# headers.net
KiCad netlist of a schematic drawn in Altium Designer
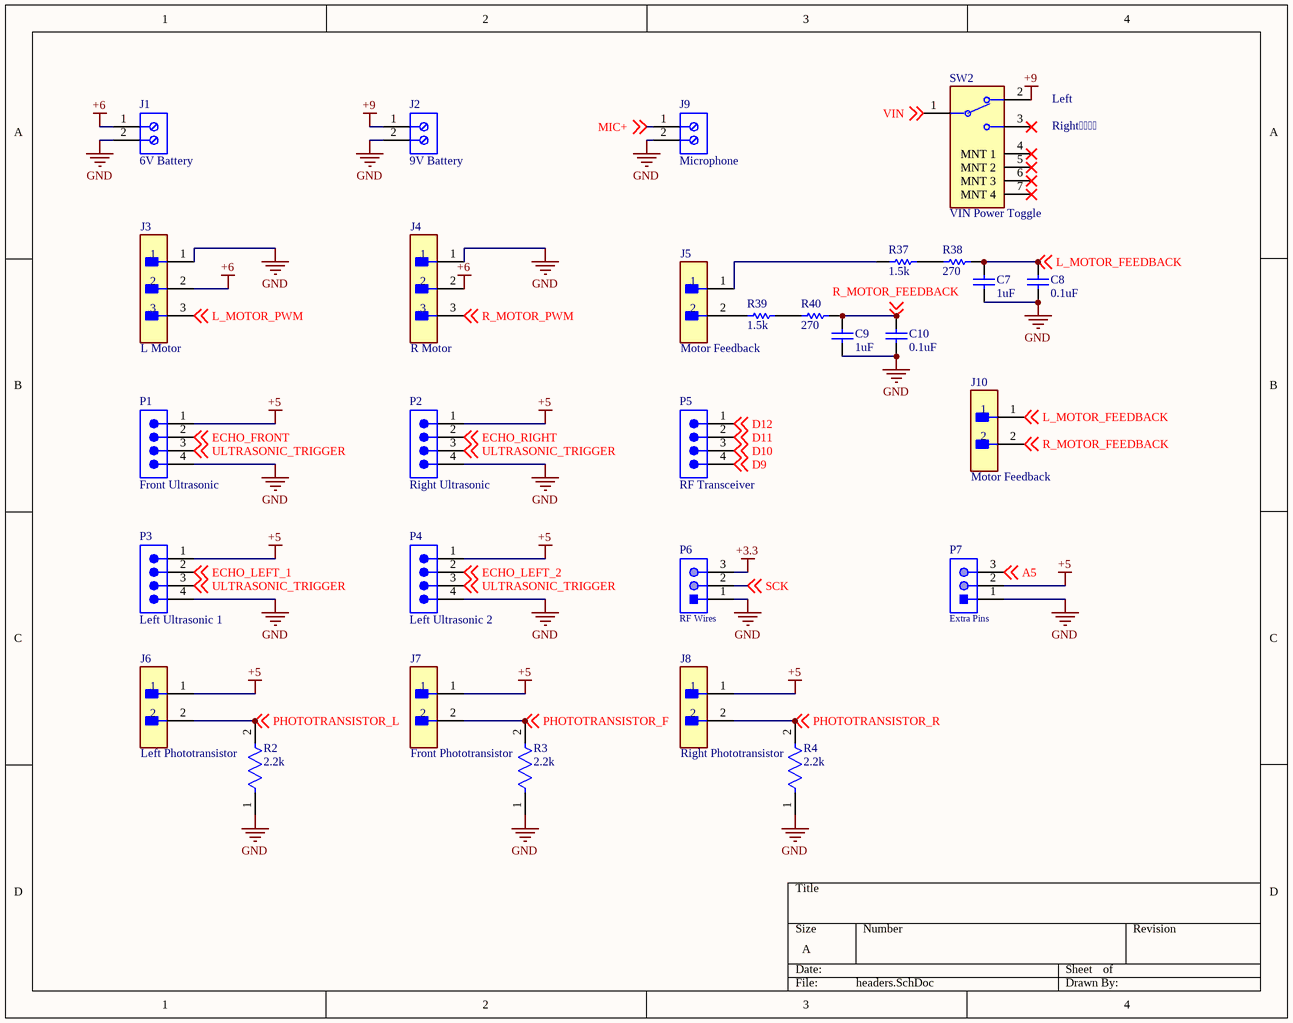
[diagram p0: headers.SchDoc]

(export (version "E")
  (design (tool "Eeschema 10.0.6"))
  (components
    (comp (ref "C7")
      (value "1uF")
      (footprint "CAPC2013X145X50LL20T25")
      (fields (field (name "MANUFACTURER") "Kemet") (field (name "PART NUMBER") "C0805C105K4PACTU"))
      (libsource (lib "Altium Content Vault") (part "CAP"))
    )
    (comp (ref "C8")
      (value "0.1uF")
      (footprint "CAPC2013X145X50LL20T25")
      (fields (field (name "MANUFACTURER") "Kemet") (field (name "PART NUMBER") "C0805C105K4PACTU"))
      (libsource (lib "Altium Content Vault") (part "CAP"))
    )
    (comp (ref "C9")
      (value "1uF")
      (footprint "CAPC2013X145X50LL20T25")
      (fields (field (name "MANUFACTURER") "Kemet") (field (name "PART NUMBER") "C0805C105K4PACTU"))
      (libsource (lib "Altium Content Vault") (part "CAP"))
    )
    (comp (ref "C10")
      (value "0.1uF")
      (footprint "CAPC2013X145X50LL20T25")
      (fields (field (name "MANUFACTURER") "Kemet") (field (name "PART NUMBER") "C0805C105K4PACTU"))
      (libsource (lib "Altium Content Vault") (part "CAP"))
    )
    (comp (ref "J1")
      (value "6V Battery")
      (footprint "691103110002")
      (description "Series 1031 - 3.50 mm Horizontal Entry Modular with Pressure Clamp WR-TBL, 2 pin")
      (fields
        (field (name "MANUFACTURER") "Wurth Elektronik")
        (field (name "PART NUMBER") "691103110002")
        (field (name "PUBLISHER") "WurthElektronik")
      )
      (libsource (lib "Altium Content Vault") (part "WE-CN-1P-F-TB2"))
    )
    (comp (ref "J2")
      (value "9V Battery")
      (footprint "691103110002")
      (description "Series 1031 - 3.50 mm Horizontal Entry Modular with Pressure Clamp WR-TBL, 2 pin")
      (fields
        (field (name "MANUFACTURER") "Wurth Elektronik")
        (field (name "PART NUMBER") "691103110002")
        (field (name "PUBLISHER") "WurthElektronik")
      )
      (libsource (lib "Altium Content Vault") (part "WE-CN-1P-F-TB2"))
    )
    (comp (ref "J3")
      (value "L Motor")
      (footprint "FP-5-104935-3-MFG")
      (description "CONN HEADER R/A 3POS 2.54MM")
      (fields (field (name "MPN") "5-104935-3"))
      (libsource (lib "Altium Content Vault") (part "0d3f023dd272f625e17a2be33dea85f"))
    )
    (comp (ref "J4")
      (value "R Motor")
      (footprint "FP-5-104935-3-MFG")
      (description "CONN HEADER R/A 3POS 2.54MM")
      (fields (field (name "MPN") "5-104935-3"))
      (libsource (lib "Altium Content Vault") (part "0d3f023dd272f625e17a2be33dea85f"))
    )
    (comp (ref "J5")
      (value "Motor Feedback")
      (footprint "FP-M20-9990246-MFG")
      (description "CONN HEADER VERT 2POS 2.54MM")
      (fields
        (field (name "OCTOPART") "https://octopart.com/m20-9990246-harwin-2590635")
        (field (name "MANUFACTURER") "Harwin")
      )
      (libsource (lib "Altium Content Vault") (part "3bc925449376181038e59eaffc5286c"))
    )
    (comp (ref "J6")
      (value "Left Phototransistor")
      (footprint "FP-M20-9990246-MFG")
      (description "Connector Header Through Hole 2 position 0.100\" (2.54mm)")
      (fields (field (name "OCTOPART") "https://octopart.com/m20-9990246-harwin-2590635"))
      (libsource (lib "Altium Content Vault") (part "3bc925449376181038e59eaffc5286c"))
    )
    (comp (ref "J7")
      (value "Front Phototransistor")
      (footprint "FP-M20-9990246-MFG")
      (description "Connector Header Through Hole 2 position 0.100\" (2.54mm)")
      (fields (field (name "OCTOPART") "https://octopart.com/m20-9990246-harwin-2590635"))
      (libsource (lib "Altium Content Vault") (part "3bc925449376181038e59eaffc5286c"))
    )
    (comp (ref "J8")
      (value "Right Phototransistor")
      (footprint "FP-M20-9990246-MFG")
      (description "Connector Header Through Hole 2 position 0.100\" (2.54mm)")
      (fields (field (name "OCTOPART") "https://octopart.com/m20-9990246-harwin-2590635"))
      (libsource (lib "Altium Content Vault") (part "3bc925449376181038e59eaffc5286c"))
    )
    (comp (ref "J9")
      (value "Microphone")
      (footprint "691103110002")
      (description "Series 1031 - 3.50 mm Horizontal Entry Modular with Pressure Clamp WR-TBL, 2 pin")
      (fields
        (field (name "MANUFACTURER") "Wurth Elektronik")
        (field (name "PART NUMBER") "691103110002")
        (field (name "PUBLISHER") "WurthElektronik")
      )
      (libsource (lib "Altium Content Vault") (part "WE-CN-1P-F-TB2"))
    )
    (comp (ref "J10")
      (value "Motor Feedback")
      (footprint "FP-M20-9990246-MFG")
      (description "CONN HEADER VERT 2POS 2.54MM")
      (fields
        (field (name "OCTOPART") "https://octopart.com/m20-9990246-harwin-2590635")
        (field (name "MANUFACTURER") "Harwin")
      )
      (libsource (lib "Altium Content Vault") (part "3bc925449376181038e59eaffc5286c"))
    )
    (comp (ref "P1")
      (value "Front Ultrasonic")
      (footprint "SMTC-TSW-104-08-X-S")
      (description "0.025\" SQ Post Header, Through-hole, Vertical, -55 to 125 degC, 2.54 mm Pitch, 4-Pin, Male, RoHS")
      (fields (field (name "MANUFACTURER") "Samtec") (field (name "PARTNUMBER") "TSW-104-08-F-S"))
      (libsource (lib "Altium Content Vault") (part "SMTC-TSW-104-08-X-S"))
    )
    (comp (ref "P2")
      (value "Right Ultrasonic")
      (footprint "SMTC-TSW-104-08-X-S")
      (description "0.025\" SQ Post Header, Through-hole, Vertical, -55 to 125 degC, 2.54 mm Pitch, 4-Pin, Male, RoHS")
      (fields (field (name "MANUFACTURER") "Samtec") (field (name "PARTNUMBER") "TSW-104-08-F-S"))
      (libsource (lib "Altium Content Vault") (part "SMTC-TSW-104-08-X-S"))
    )
    (comp (ref "P3")
      (value "Left Ultrasonic 1")
      (footprint "SMTC-TSW-104-08-X-S")
      (description "0.025\" SQ Post Header, Through-hole, Vertical, -55 to 125 degC, 2.54 mm Pitch, 4-Pin, Male, RoHS")
      (fields (field (name "MANUFACTURER") "Samtec") (field (name "PARTNUMBER") "TSW-104-08-F-S"))
      (libsource (lib "Altium Content Vault") (part "SMTC-TSW-104-08-X-S"))
    )
    (comp (ref "P4")
      (value "Left Ultrasonic 2")
      (footprint "SMTC-TSW-104-08-X-S")
      (description "0.025\" SQ Post Header, Through-hole, Vertical, -55 to 125 degC, 2.54 mm Pitch, 4-Pin, Male, RoHS")
      (fields (field (name "MANUFACTURER") "Samtec") (field (name "PARTNUMBER") "TSW-104-08-F-S"))
      (libsource (lib "Altium Content Vault") (part "SMTC-TSW-104-08-X-S"))
    )
    (comp (ref "P5")
      (value "RF Transceiver")
      (footprint "SMTC-TSW-104-08-X-S")
      (description "0.025\" SQ Post Header, Through-hole, Vertical, -55 to 125 degC, 2.54 mm Pitch, 4-Pin, Male, RoHS")
      (fields (field (name "MANUFACTURER") "Samtec") (field (name "PARTNUMBER") "TSW-104-08-F-S"))
      (libsource (lib "Altium Content Vault") (part "SMTC-TSW-104-08-X-S"))
    )
    (comp (ref "P6")
      (value "RF Wires")
      (footprint "61300311121")
      (description "THT Vertical Pin Header WR-PHD, Pitch 2.54 mm, Single Row, 3 pins")
      (fields
        (field (name "PART NUMBER") "61300311121")
        (field (name "MANUFACTURER") "Wurth Elektronik")
        (field (name "PUBLISHER") "WurthElektronik")
      )
      (libsource (lib "Altium Content Vault") (part "WE-CN-1P-M-R3"))
    )
    (comp (ref "P7")
      (value "Extra Pins")
      (footprint "61300311121")
      (description "THT Vertical Pin Header WR-PHD, Pitch 2.54 mm, Single Row, 3 pins")
      (fields
        (field (name "PART NUMBER") "61300311121")
        (field (name "MANUFACTURER") "Wurth Elektronik")
        (field (name "PUBLISHER") "WurthElektronik")
      )
      (libsource (lib "Altium Content Vault") (part "WE-CN-1P-M-R3"))
    )
    (comp (ref "R2")
      (value "2.2k")
      (footprint "FP-CRCW0805-e3-IPC_B")
      (description "RES Thick Film, 2.2kΩ, 1%, 0.125W, 100ppm/°C, 0805")
      (fields (field (name "TOLERANCE") "1%") (field (name "MPN") "CRCW08052K20FKEA"))
      (libsource (lib "Altium Content Vault") (part "1029c3af85768c4190bb7ad29bc67b5"))
    )
    (comp (ref "R3")
      (value "2.2k")
      (footprint "FP-CRCW0805-e3-IPC_B")
      (description "RES Thick Film, 2.2kΩ, 1%, 0.125W, 100ppm/°C, 0805")
      (fields (field (name "TOLERANCE") "1%") (field (name "MPN") "CRCW08052K20FKEA"))
      (libsource (lib "Altium Content Vault") (part "1029c3af85768c4190bb7ad29bc67b5"))
    )
    (comp (ref "R4")
      (value "2.2k")
      (footprint "FP-CRCW0805-e3-IPC_B")
      (description "RES Thick Film, 2.2kΩ, 1%, 0.125W, 100ppm/°C, 0805")
      (fields (field (name "TOLERANCE") "1%") (field (name "MPN") "CRCW08052K20FKEA"))
      (libsource (lib "Altium Content Vault") (part "1029c3af85768c4190bb7ad29bc67b5"))
    )
    (comp (ref "R37")
      (value "1.5k")
      (footprint "RESC1609X50X30NL8T20")
      (description "Chip Resistor, 10 KOhm, +/- 1%, 100 mW, -55 to 155 degC, 0603 (1608 Metric), RoHS, Tape and Reel")
      (fields (field (name "MANUFACTURER") "Vishay Semiconductor"))
      (libsource (lib "Altium Content Vault") (part "RES-2"))
    )
    (comp (ref "R38")
      (value "270")
      (footprint "RESC1609X50X30NL8T20")
      (description "Chip Resistor, 10 KOhm, +/- 1%, 100 mW, -55 to 155 degC, 0603 (1608 Metric), RoHS, Tape and Reel")
      (fields (field (name "MANUFACTURER") "Vishay Semiconductor"))
      (libsource (lib "Altium Content Vault") (part "RES-2"))
    )
    (comp (ref "R39")
      (value "1.5k")
      (footprint "RESC1609X50X30NL8T20")
      (description "Chip Resistor, 10 KOhm, +/- 1%, 100 mW, -55 to 155 degC, 0603 (1608 Metric), RoHS, Tape and Reel")
      (fields (field (name "MANUFACTURER") "Vishay Semiconductor"))
      (libsource (lib "Altium Content Vault") (part "RES-2"))
    )
    (comp (ref "R40")
      (value "270")
      (footprint "RESC1609X50X30NL8T20")
      (description "Chip Resistor, 10 KOhm, +/- 1%, 100 mW, -55 to 155 degC, 0603 (1608 Metric), RoHS, Tape and Reel")
      (fields (field (name "MANUFACTURER") "Vishay Semiconductor"))
      (libsource (lib "Altium Content Vault") (part "RES-2"))
    )
    (comp (ref "SW2")
      (value "VIN Power Toggle")
      (footprint "FP-PCM12SMTR-MFG")
      (description "SWITCH SLIDE SPDT 300MA 6V")
      (fields (field (name "MPN") "PCM12SMTR"))
      (libsource (lib "Altium Content Vault") (part "1a3f67d7e2b5469b171eeab59ffb4d2"))
    )
  )
  (nets
    (net (code "1") (name "+3.3") (class "Default")
      (node (ref "P6") (pin "3") (pinfunction "3_3") (pintype "passive"))
    )
    (net (code "2") (name "+5") (class "Default")
      (node (ref "J6") (pin "1") (pinfunction "1_1") (pintype "passive"))
      (node (ref "J7") (pin "1") (pinfunction "1_1") (pintype "passive"))
      (node (ref "J8") (pin "1") (pinfunction "1_1") (pintype "passive"))
      (node (ref "P1") (pin "1") (pinfunction "1_1") (pintype "passive"))
      (node (ref "P2") (pin "1") (pinfunction "1_1") (pintype "passive"))
      (node (ref "P3") (pin "1") (pinfunction "1_1") (pintype "passive"))
      (node (ref "P4") (pin "1") (pinfunction "1_1") (pintype "passive"))
      (node (ref "P7") (pin "2") (pinfunction "2_2") (pintype "passive"))
    )
    (net (code "3") (name "+6") (class "Default")
      (node (ref "J1") (pin "1") (pinfunction "1_1") (pintype "passive"))
      (node (ref "J3") (pin "2") (pinfunction "2_2") (pintype "passive"))
      (node (ref "J4") (pin "2") (pinfunction "2_2") (pintype "passive"))
    )
    (net (code "4") (name "+9") (class "Default")
      (node (ref "J2") (pin "1") (pinfunction "1_1") (pintype "passive"))
      (node (ref "SW2") (pin "2") (pinfunction "2_2") (pintype "passive"))
    )
    (net (code "5") (name "A5") (class "Default")
      (node (ref "P7") (pin "3") (pinfunction "3_3") (pintype "passive"))
    )
    (net (code "6") (name "D9") (class "Default")
      (node (ref "P5") (pin "4") (pinfunction "4_4") (pintype "passive"))
    )
    (net (code "7") (name "D10") (class "Default")
      (node (ref "P5") (pin "3") (pinfunction "3_3") (pintype "passive"))
    )
    (net (code "8") (name "D11") (class "Default")
      (node (ref "P5") (pin "2") (pinfunction "2_2") (pintype "passive"))
    )
    (net (code "9") (name "D12") (class "Default")
      (node (ref "P5") (pin "1") (pinfunction "1_1") (pintype "passive"))
    )
    (net (code "10") (name "ECHO_FRONT") (class "Default")
      (node (ref "P1") (pin "2") (pinfunction "2_2") (pintype "passive"))
    )
    (net (code "11") (name "ECHO_LEFT_1") (class "Default")
      (node (ref "P3") (pin "2") (pinfunction "2_2") (pintype "passive"))
    )
    (net (code "12") (name "ECHO_LEFT_2") (class "Default")
      (node (ref "P4") (pin "2") (pinfunction "2_2") (pintype "passive"))
    )
    (net (code "13") (name "ECHO_RIGHT") (class "Default")
      (node (ref "P2") (pin "2") (pinfunction "2_2") (pintype "passive"))
    )
    (net (code "14") (name "GND") (class "Default")
      (node (ref "C10") (pin "1") (pinfunction "1_1") (pintype "passive"))
      (node (ref "C7") (pin "1") (pinfunction "1_1") (pintype "passive"))
      (node (ref "C8") (pin "1") (pinfunction "1_1") (pintype "passive"))
      (node (ref "C9") (pin "2") (pinfunction "2_2") (pintype "passive"))
      (node (ref "J1") (pin "2") (pinfunction "2_2") (pintype "passive"))
      (node (ref "J2") (pin "2") (pinfunction "2_2") (pintype "passive"))
      (node (ref "J3") (pin "1") (pinfunction "1_1") (pintype "passive"))
      (node (ref "J4") (pin "1") (pinfunction "1_1") (pintype "passive"))
      (node (ref "J9") (pin "2") (pinfunction "2_2") (pintype "passive"))
      (node (ref "P1") (pin "4") (pinfunction "4_4") (pintype "passive"))
      (node (ref "P2") (pin "4") (pinfunction "4_4") (pintype "passive"))
      (node (ref "P3") (pin "4") (pinfunction "4_4") (pintype "passive"))
      (node (ref "P4") (pin "4") (pinfunction "4_4") (pintype "passive"))
      (node (ref "P6") (pin "1") (pinfunction "1_1") (pintype "passive"))
      (node (ref "P7") (pin "1") (pinfunction "1_1") (pintype "passive"))
      (node (ref "R2") (pin "1") (pinfunction "1_1") (pintype "passive"))
      (node (ref "R3") (pin "1") (pinfunction "1_1") (pintype "passive"))
      (node (ref "R4") (pin "1") (pinfunction "1_1") (pintype "passive"))
    )
    (net (code "15") (name "L_MOTOR_FEEDBACK") (class "Default")
      (node (ref "C7") (pin "2") (pinfunction "2_2") (pintype "passive"))
      (node (ref "C8") (pin "2") (pinfunction "2_2") (pintype "passive"))
      (node (ref "J10") (pin "1") (pinfunction "1_1") (pintype "passive"))
      (node (ref "R38") (pin "2") (pinfunction "2_2") (pintype "passive"))
    )
    (net (code "16") (name "L_MOTOR_PWM") (class "Default")
      (node (ref "J3") (pin "3") (pinfunction "3_3") (pintype "passive"))
    )
    (net (code "17") (name "MIC+") (class "Default")
      (node (ref "J9") (pin "1") (pinfunction "1_1") (pintype "passive"))
    )
    (net (code "18") (name "Net-(J5-Pad1)") (class "Default")
      (node (ref "J5") (pin "1") (pinfunction "1_1") (pintype "passive"))
      (node (ref "R37") (pin "1") (pinfunction "1_1") (pintype "passive"))
    )
    (net (code "19") (name "Net-(J5-Pad2)") (class "Default")
      (node (ref "J5") (pin "2") (pinfunction "2_2") (pintype "passive"))
      (node (ref "R39") (pin "1") (pinfunction "1_1") (pintype "passive"))
    )
    (net (code "20") (name "Net-(R37-Pad2)") (class "Default")
      (node (ref "R37") (pin "2") (pinfunction "2_2") (pintype "passive"))
      (node (ref "R38") (pin "1") (pinfunction "1_1") (pintype "passive"))
    )
    (net (code "21") (name "Net-(R39-Pad2)") (class "Default")
      (node (ref "R39") (pin "2") (pinfunction "2_2") (pintype "passive"))
      (node (ref "R40") (pin "1") (pinfunction "1_1") (pintype "passive"))
    )
    (net (code "22") (name "PHOTOTRANSISTOR_F") (class "Default")
      (node (ref "J7") (pin "2") (pinfunction "2_2") (pintype "passive"))
      (node (ref "R3") (pin "2") (pinfunction "2_2") (pintype "passive"))
    )
    (net (code "23") (name "PHOTOTRANSISTOR_L") (class "Default")
      (node (ref "J6") (pin "2") (pinfunction "2_2") (pintype "passive"))
      (node (ref "R2") (pin "2") (pinfunction "2_2") (pintype "passive"))
    )
    (net (code "24") (name "PHOTOTRANSISTOR_R") (class "Default")
      (node (ref "J8") (pin "2") (pinfunction "2_2") (pintype "passive"))
      (node (ref "R4") (pin "2") (pinfunction "2_2") (pintype "passive"))
    )
    (net (code "25") (name "R_MOTOR_FEEDBACK") (class "Default")
      (node (ref "C10") (pin "2") (pinfunction "2_2") (pintype "passive"))
      (node (ref "C9") (pin "1") (pinfunction "1_1") (pintype "passive"))
      (node (ref "J10") (pin "2") (pinfunction "2_2") (pintype "passive"))
      (node (ref "R40") (pin "2") (pinfunction "2_2") (pintype "passive"))
    )
    (net (code "26") (name "R_MOTOR_PWM") (class "Default")
      (node (ref "J4") (pin "3") (pinfunction "3_3") (pintype "passive"))
    )
    (net (code "27") (name "SCK") (class "Default")
      (node (ref "P6") (pin "2") (pinfunction "2_2") (pintype "passive"))
    )
    (net (code "28") (name "ULTRASONIC_TRIGGER") (class "Default")
      (node (ref "P1") (pin "3") (pinfunction "3_3") (pintype "passive"))
      (node (ref "P2") (pin "3") (pinfunction "3_3") (pintype "passive"))
      (node (ref "P3") (pin "3") (pinfunction "3_3") (pintype "passive"))
      (node (ref "P4") (pin "3") (pinfunction "3_3") (pintype "passive"))
    )
    (net (code "29") (name "VIN") (class "Default")
      (node (ref "SW2") (pin "1") (pinfunction "1_1") (pintype "passive"))
    )
    (net (code "30") (name "unconnected-(SW2-MNT_1-Pad4)") (class "Default")
      (node (ref "SW2") (pin "4") (pinfunction "MNT_1_4") (pintype "passive+no_connect"))
    )
    (net (code "31") (name "unconnected-(SW2-MNT_2-Pad5)") (class "Default")
      (node (ref "SW2") (pin "5") (pinfunction "MNT_2_5") (pintype "passive+no_connect"))
    )
    (net (code "32") (name "unconnected-(SW2-MNT_3-Pad6)") (class "Default")
      (node (ref "SW2") (pin "6") (pinfunction "MNT_3_6") (pintype "passive+no_connect"))
    )
    (net (code "33") (name "unconnected-(SW2-MNT_4-Pad7)") (class "Default")
      (node (ref "SW2") (pin "7") (pinfunction "MNT_4_7") (pintype "passive+no_connect"))
    )
    (net (code "34") (name "unconnected-(SW2-Pad3)") (class "Default")
      (node (ref "SW2") (pin "3") (pinfunction "3_3") (pintype "passive+no_connect"))
    )
  )
)
